# spi-interface-TFML.net
KiCad netlist of a schematic drawn in EAGLE
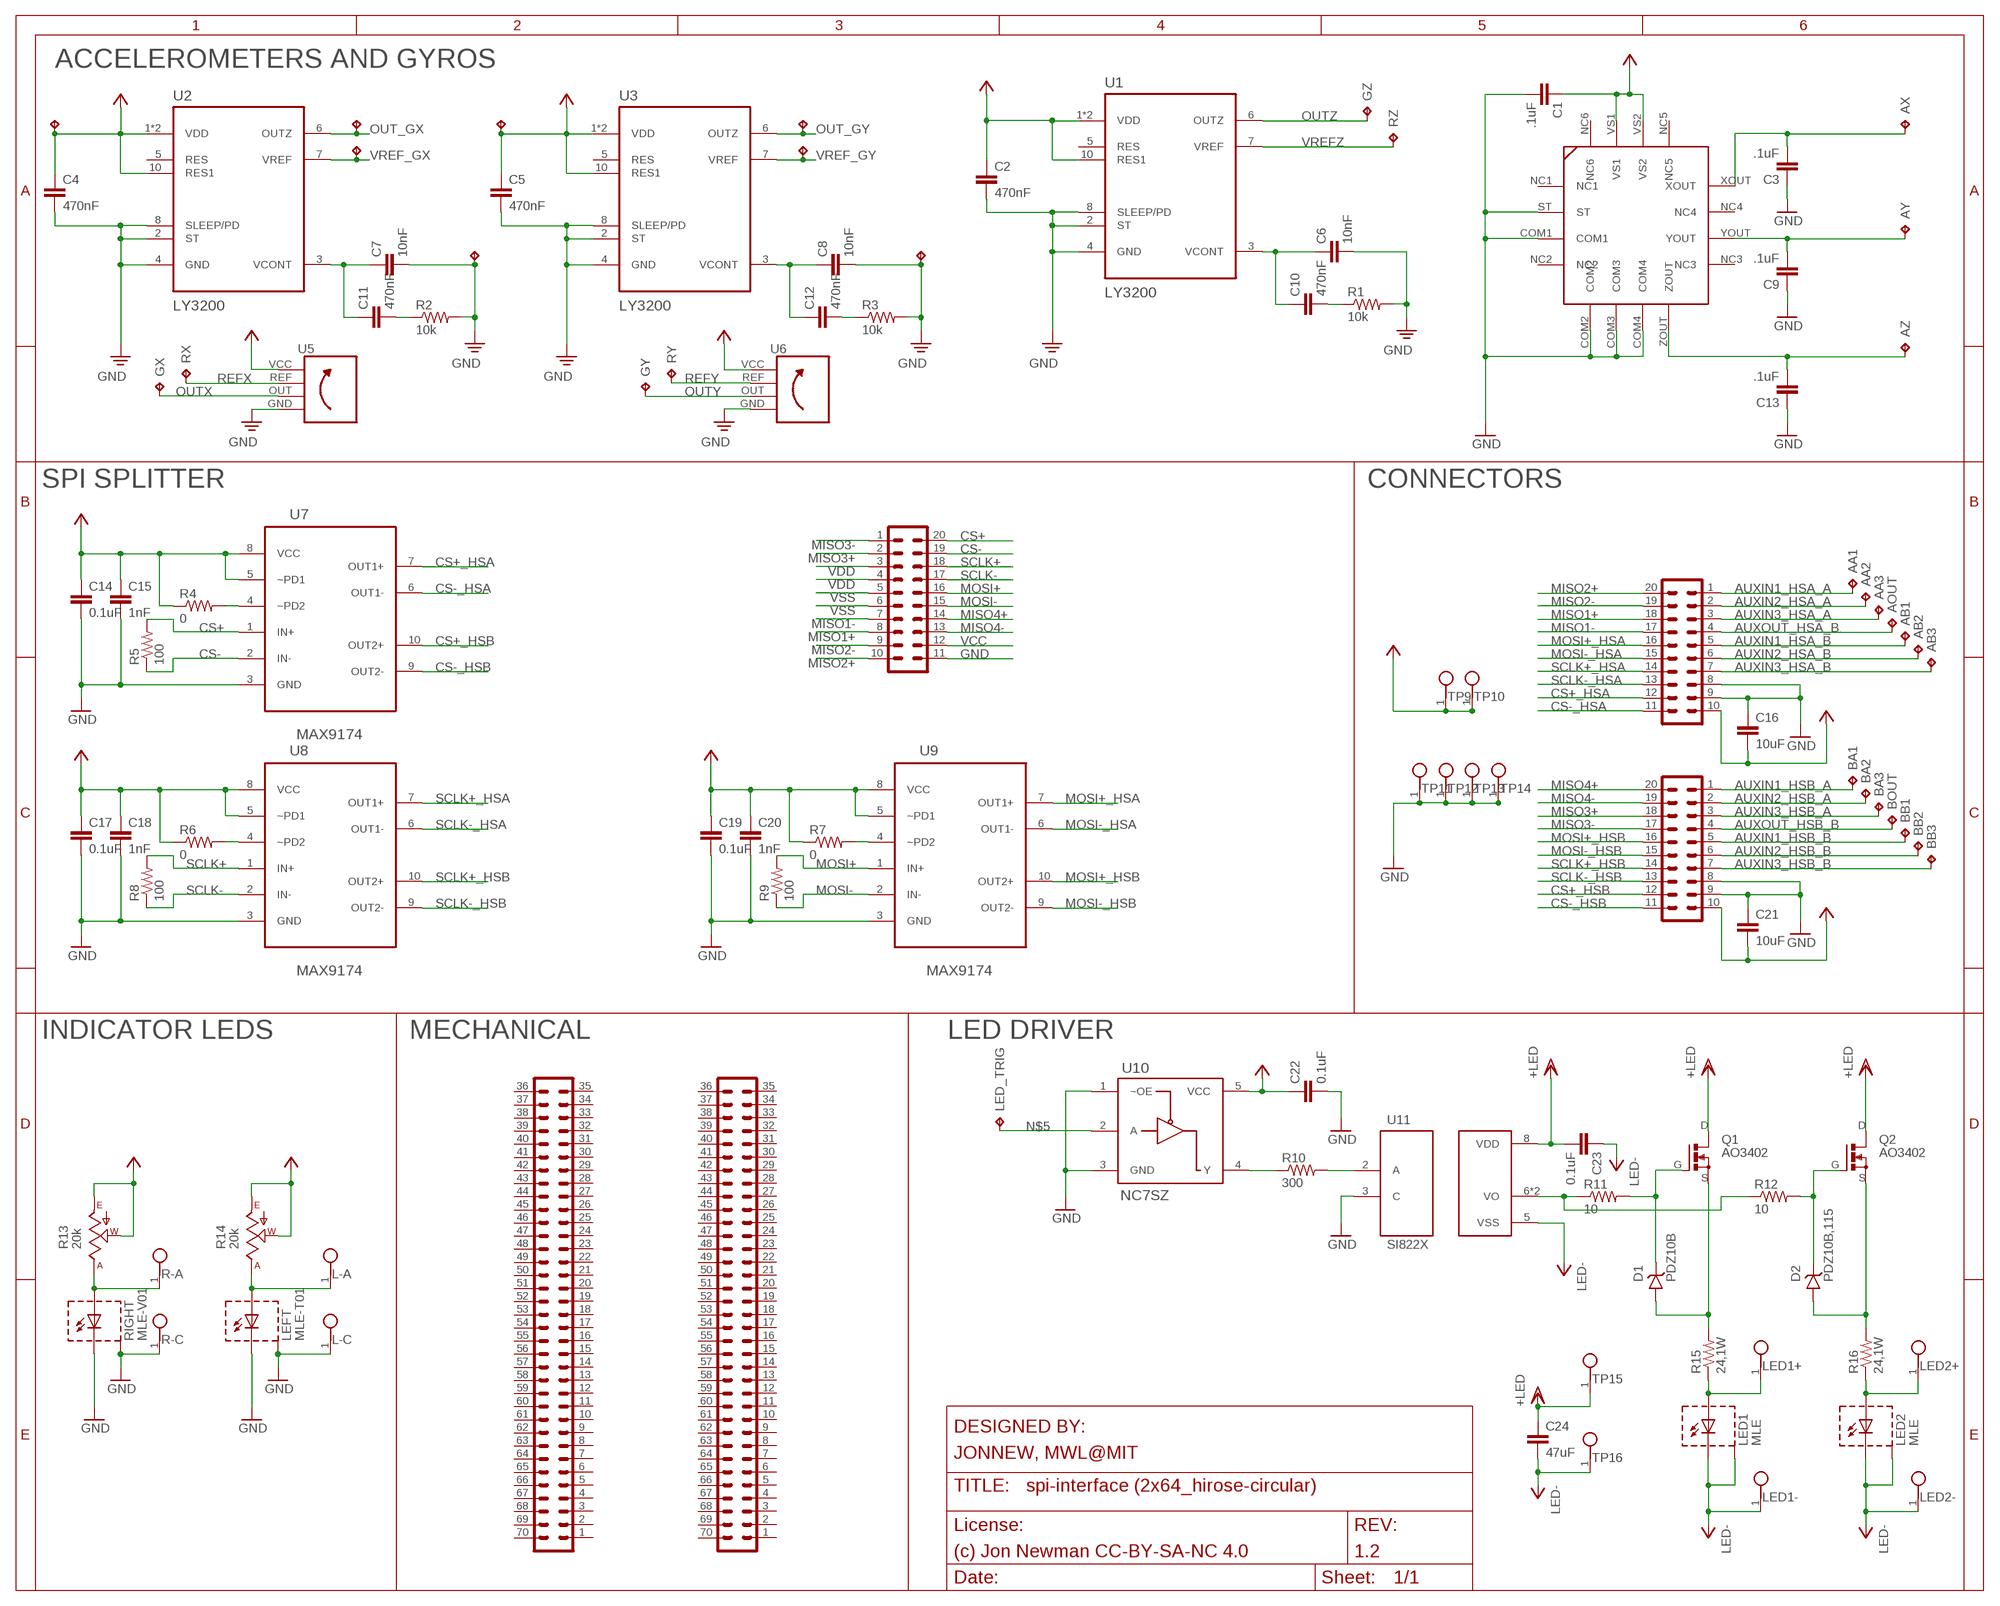
[diagram p0: schematic, sheet 1]

(export (version "E")
  (design (tool "Eeschema 10.0.6"))
  (components
    (comp (ref "AA1")
      (value "TP_0.5MM")
      (footprint "eagle-import:TESTPOINT_0.5MM")
      (libsource (lib "eagle-import") (part "TP_0.5MM"))
    )
    (comp (ref "AA2")
      (value "TP_0.5MM")
      (footprint "eagle-import:TESTPOINT_0.5MM")
      (libsource (lib "eagle-import") (part "TP_0.5MM"))
    )
    (comp (ref "AA3")
      (value "TP_0.5MM")
      (footprint "eagle-import:TESTPOINT_0.5MM")
      (libsource (lib "eagle-import") (part "TP_0.5MM"))
    )
    (comp (ref "AB1")
      (value "TP_0.5MM")
      (footprint "eagle-import:TESTPOINT_0.5MM")
      (libsource (lib "eagle-import") (part "TP_0.5MM"))
    )
    (comp (ref "AB2")
      (value "TP_0.5MM")
      (footprint "eagle-import:TESTPOINT_0.5MM")
      (libsource (lib "eagle-import") (part "TP_0.5MM"))
    )
    (comp (ref "AB3")
      (value "TP_0.5MM")
      (footprint "eagle-import:TESTPOINT_0.5MM")
      (libsource (lib "eagle-import") (part "TP_0.5MM"))
    )
    (comp (ref "AOUT")
      (value "TP_0.5MM")
      (footprint "eagle-import:TESTPOINT_0.5MM")
      (libsource (lib "eagle-import") (part "TP_0.5MM"))
    )
    (comp (ref "AX")
      (value "TP_0.5MM")
      (footprint "eagle-import:TESTPOINT_0.5MM")
      (libsource (lib "eagle-import") (part "TP_0.5MM"))
    )
    (comp (ref "AY")
      (value "TP_0.5MM")
      (footprint "eagle-import:TESTPOINT_0.5MM")
      (libsource (lib "eagle-import") (part "TP_0.5MM"))
    )
    (comp (ref "AZ")
      (value "TP_0.5MM")
      (footprint "eagle-import:TESTPOINT_0.5MM")
      (libsource (lib "eagle-import") (part "TP_0.5MM"))
    )
    (comp (ref "BA1")
      (value "TP_0.5MM")
      (footprint "eagle-import:TESTPOINT_0.5MM")
      (libsource (lib "eagle-import") (part "TP_0.5MM"))
    )
    (comp (ref "BA2")
      (value "TP_0.5MM")
      (footprint "eagle-import:TESTPOINT_0.5MM")
      (libsource (lib "eagle-import") (part "TP_0.5MM"))
    )
    (comp (ref "BA3")
      (value "TP_0.5MM")
      (footprint "eagle-import:TESTPOINT_0.5MM")
      (libsource (lib "eagle-import") (part "TP_0.5MM"))
    )
    (comp (ref "BB1")
      (value "TP_0.5MM")
      (footprint "eagle-import:TESTPOINT_0.5MM")
      (libsource (lib "eagle-import") (part "TP_0.5MM"))
    )
    (comp (ref "BB2")
      (value "TP_0.5MM")
      (footprint "eagle-import:TESTPOINT_0.5MM")
      (libsource (lib "eagle-import") (part "TP_0.5MM"))
    )
    (comp (ref "BB3")
      (value "TP_0.5MM")
      (footprint "eagle-import:TESTPOINT_0.5MM")
      (libsource (lib "eagle-import") (part "TP_0.5MM"))
    )
    (comp (ref "BOUT")
      (value "TP_0.5MM")
      (footprint "eagle-import:TESTPOINT_0.5MM")
      (libsource (lib "eagle-import") (part "TP_0.5MM"))
    )
    (comp (ref "C1")
      (value ".1uF")
      (footprint "eagle-import:0402")
      (libsource (lib "eagle-import") (part "C_0402"))
    )
    (comp (ref "C2")
      (value "470nF")
      (footprint "eagle-import:0201")
      (libsource (lib "eagle-import") (part "jonnew_C_0201"))
    )
    (comp (ref "C3")
      (value ".1uF")
      (footprint "eagle-import:0201")
      (libsource (lib "eagle-import") (part "jonnew_C_0201"))
    )
    (comp (ref "C4")
      (value "470nF")
      (footprint "eagle-import:0201")
      (libsource (lib "eagle-import") (part "jonnew_C_0201"))
    )
    (comp (ref "C5")
      (value "470nF")
      (footprint "eagle-import:0201")
      (libsource (lib "eagle-import") (part "jonnew_C_0201"))
    )
    (comp (ref "C6")
      (value "10nF")
      (footprint "eagle-import:0201")
      (libsource (lib "eagle-import") (part "jonnew_C_0201"))
    )
    (comp (ref "C7")
      (value "10nF")
      (footprint "eagle-import:0201")
      (libsource (lib "eagle-import") (part "jonnew_C_0201"))
    )
    (comp (ref "C8")
      (value "10nF")
      (footprint "eagle-import:0201")
      (libsource (lib "eagle-import") (part "jonnew_C_0201"))
    )
    (comp (ref "C9")
      (value ".1uF")
      (footprint "eagle-import:0201")
      (libsource (lib "eagle-import") (part "jonnew_C_0201"))
    )
    (comp (ref "C10")
      (value "470nF")
      (footprint "eagle-import:0201")
      (libsource (lib "eagle-import") (part "jonnew_C_0201"))
    )
    (comp (ref "C11")
      (value "470nF")
      (footprint "eagle-import:0201")
      (libsource (lib "eagle-import") (part "jonnew_C_0201"))
    )
    (comp (ref "C12")
      (value "470nF")
      (footprint "eagle-import:0201")
      (libsource (lib "eagle-import") (part "jonnew_C_0201"))
    )
    (comp (ref "C13")
      (value ".1uF")
      (footprint "eagle-import:0201")
      (libsource (lib "eagle-import") (part "jonnew_C_0201"))
    )
    (comp (ref "C14")
      (value "0.1uF")
      (footprint "eagle-import:0402")
      (libsource (lib "eagle-import") (part "jonnew_C_0402"))
    )
    (comp (ref "C15")
      (value "1nF")
      (footprint "eagle-import:0201")
      (libsource (lib "eagle-import") (part "jonnew_C_0201"))
    )
    (comp (ref "C16")
      (value "10uF")
      (footprint "eagle-import:0805")
      (fields (field (name "PARTNO") "C2012X5R1Cxxxxxxx"))
      (libsource (lib "eagle-import") (part "C_0805"))
    )
    (comp (ref "C17")
      (value "0.1uF")
      (footprint "eagle-import:0402")
      (libsource (lib "eagle-import") (part "jonnew_C_0402"))
    )
    (comp (ref "C18")
      (value "1nF")
      (footprint "eagle-import:0201")
      (libsource (lib "eagle-import") (part "jonnew_C_0201"))
    )
    (comp (ref "C19")
      (value "0.1uF")
      (footprint "eagle-import:0402")
      (libsource (lib "eagle-import") (part "jonnew_C_0402"))
    )
    (comp (ref "C20")
      (value "1nF")
      (footprint "eagle-import:0201")
      (libsource (lib "eagle-import") (part "jonnew_C_0201"))
    )
    (comp (ref "C21")
      (value "10uF")
      (footprint "eagle-import:0805")
      (fields (field (name "PARTNO") "C2012X5R1Cxxxxxxx"))
      (libsource (lib "eagle-import") (part "C_0805"))
    )
    (comp (ref "C22")
      (value "0.1uF")
      (footprint "eagle-import:0402")
      (libsource (lib "eagle-import") (part "jonnew_C_0402"))
    )
    (comp (ref "C23")
      (value "0.1uF")
      (footprint "eagle-import:0402")
      (libsource (lib "eagle-import") (part "jonnew_C_0402"))
    )
    (comp (ref "C24")
      (value "47uF")
      (footprint "eagle-import:1206")
      (libsource (lib "eagle-import") (part "jonnew_C_1206"))
    )
    (comp (ref "D1")
      (value "PDZ10B")
      (footprint "eagle-import:SOD-323")
      (libsource (lib "eagle-import") (part "Z-DIODE_SOD-323"))
    )
    (comp (ref "D2")
      (value "PDZ10B,115")
      (footprint "eagle-import:SOD-323")
      (libsource (lib "eagle-import") (part "Z-DIODE_SOD-323"))
    )
    (comp (ref "DIO_HSA")
      (value "PINHD-2X10_DF40-20REC")
      (footprint "eagle-import:DF40-20REC")
      (libsource (lib "eagle-import") (part "PINHD-2X10_DF40-20REC"))
    )
    (comp (ref "DIO_HSB")
      (value "PINHD-2X10_DF40-20REC")
      (footprint "eagle-import:DF40-20REC")
      (libsource (lib "eagle-import") (part "PINHD-2X10_DF40-20REC"))
    )
    (comp (ref "GX")
      (value "TP_0.5MM")
      (footprint "eagle-import:TESTPOINT_0.5MM")
      (libsource (lib "eagle-import") (part "TP_0.5MM"))
    )
    (comp (ref "GY")
      (value "TP_0.5MM")
      (footprint "eagle-import:TESTPOINT_0.5MM")
      (libsource (lib "eagle-import") (part "TP_0.5MM"))
    )
    (comp (ref "GZ")
      (value "TP_0.5MM")
      (footprint "eagle-import:TESTPOINT_0.5MM")
      (libsource (lib "eagle-import") (part "TP_0.5MM"))
    )
    (comp (ref "L-A")
      (value "TESTPOINT_SMALL")
      (footprint "eagle-import:TESTPOINT_SMALL")
      (libsource (lib "eagle-import") (part "TESTPOINT_SMALL"))
    )
    (comp (ref "L-C")
      (value "TESTPOINT_SMALL")
      (footprint "eagle-import:TESTPOINT_SMALL")
      (libsource (lib "eagle-import") (part "TESTPOINT_SMALL"))
    )
    (comp (ref "LED1")
      (value "MLE")
      (footprint "eagle-import:LED-MLE")
      (libsource (lib "eagle-import") (part "LED_PKG-BODY"))
    )
    (comp (ref "LED1+")
      (value "TESTPOINT_SMALL")
      (footprint "eagle-import:TESTPOINT_SMALL")
      (libsource (lib "eagle-import") (part "TESTPOINT_SMALL"))
    )
    (comp (ref "LED1-")
      (value "TESTPOINT_SMALL")
      (footprint "eagle-import:TESTPOINT_SMALL")
      (libsource (lib "eagle-import") (part "TESTPOINT_SMALL"))
    )
    (comp (ref "LED2")
      (value "MLE")
      (footprint "eagle-import:LED-MLE")
      (libsource (lib "eagle-import") (part "LED_PKG-BODY"))
    )
    (comp (ref "LED2+")
      (value "TESTPOINT_SMALL")
      (footprint "eagle-import:TESTPOINT_SMALL")
      (libsource (lib "eagle-import") (part "TESTPOINT_SMALL"))
    )
    (comp (ref "LED2-")
      (value "TESTPOINT_SMALL")
      (footprint "eagle-import:TESTPOINT_SMALL")
      (libsource (lib "eagle-import") (part "TESTPOINT_SMALL"))
    )
    (comp (ref "LED_TRIG")
      (value "TP_0.5MM")
      (footprint "eagle-import:TESTPOINT_0.5MM")
      (libsource (lib "eagle-import") (part "TP_0.5MM"))
    )
    (comp (ref "LEFT")
      (value "MLE-T01")
      (footprint "eagle-import:LED-MLE")
      (libsource (lib "eagle-import") (part "LED_PKG-BODY"))
    )
    (comp (ref "MECH_E0B")
      (value "PINHD-2X35_DF40REC")
      (footprint "eagle-import:DF40-70REC")
      (libsource (lib "eagle-import") (part "PINHD-2X35_DF40REC"))
    )
    (comp (ref "MECH_W0B")
      (value "PINHD-2X35_DF40REC")
      (footprint "eagle-import:DF40-70REC")
      (libsource (lib "eagle-import") (part "PINHD-2X35_DF40REC"))
    )
    (comp (ref "Q1")
      (value "AO3402")
      (footprint "eagle-import:SOT23-GSD")
      (libsource (lib "eagle-import") (part "N-MOSFET_SOT23-GSD"))
    )
    (comp (ref "Q2")
      (value "AO3402")
      (footprint "eagle-import:SOT23-GSD")
      (libsource (lib "eagle-import") (part "N-MOSFET_SOT23-GSD"))
    )
    (comp (ref "R-A")
      (value "TESTPOINT_SMALL")
      (footprint "eagle-import:TESTPOINT_SMALL")
      (libsource (lib "eagle-import") (part "TESTPOINT_SMALL"))
    )
    (comp (ref "R-C")
      (value "TESTPOINT_SMALL")
      (footprint "eagle-import:TESTPOINT_SMALL")
      (libsource (lib "eagle-import") (part "TESTPOINT_SMALL"))
    )
    (comp (ref "R1")
      (value "10k")
      (footprint "eagle-import:0201")
      (libsource (lib "eagle-import") (part "R_0201"))
    )
    (comp (ref "R2")
      (value "10k")
      (footprint "eagle-import:0201")
      (libsource (lib "eagle-import") (part "R_0201"))
    )
    (comp (ref "R3")
      (value "10k")
      (footprint "eagle-import:0201")
      (libsource (lib "eagle-import") (part "R_0201"))
    )
    (comp (ref "R4")
      (value "0")
      (footprint "eagle-import:0201")
      (libsource (lib "eagle-import") (part "R_0201"))
    )
    (comp (ref "R5")
      (value "100")
      (footprint "eagle-import:0201")
      (libsource (lib "eagle-import") (part "R_0201"))
    )
    (comp (ref "R6")
      (value "0")
      (footprint "eagle-import:0201")
      (libsource (lib "eagle-import") (part "R_0201"))
    )
    (comp (ref "R7")
      (value "0")
      (footprint "eagle-import:0201")
      (libsource (lib "eagle-import") (part "R_0201"))
    )
    (comp (ref "R8")
      (value "100")
      (footprint "eagle-import:0201")
      (libsource (lib "eagle-import") (part "R_0201"))
    )
    (comp (ref "R9")
      (value "100")
      (footprint "eagle-import:0201")
      (libsource (lib "eagle-import") (part "R_0201"))
    )
    (comp (ref "R10")
      (value "300")
      (footprint "eagle-import:0402")
      (libsource (lib "eagle-import") (part "R_0402"))
    )
    (comp (ref "R11")
      (value "10")
      (footprint "eagle-import:0402")
      (libsource (lib "eagle-import") (part "R_0402"))
    )
    (comp (ref "R12")
      (value "10")
      (footprint "eagle-import:0402")
      (libsource (lib "eagle-import") (part "R_0402"))
    )
    (comp (ref "R13")
      (value "20k")
      (footprint "eagle-import:SM-42_43W")
      (libsource (lib "eagle-import") (part "TRIM_US-SM-42/43W"))
    )
    (comp (ref "R14")
      (value "20k")
      (footprint "eagle-import:SM-42_43W")
      (libsource (lib "eagle-import") (part "TRIM_US-SM-42/43W"))
    )
    (comp (ref "R15")
      (value "24,1W")
      (footprint "eagle-import:0805")
      (libsource (lib "eagle-import") (part "R_0805"))
    )
    (comp (ref "R16")
      (value "24,1W")
      (footprint "eagle-import:0805")
      (libsource (lib "eagle-import") (part "R_0805"))
    )
    (comp (ref "RIGHT")
      (value "MLE-V01")
      (footprint "eagle-import:LED-MLE")
      (libsource (lib "eagle-import") (part "LED_PKG-BODY"))
    )
    (comp (ref "RX")
      (value "TP_0.5MM")
      (footprint "eagle-import:TESTPOINT_0.5MM")
      (libsource (lib "eagle-import") (part "TP_0.5MM"))
    )
    (comp (ref "RY")
      (value "TP_0.5MM")
      (footprint "eagle-import:TESTPOINT_0.5MM")
      (libsource (lib "eagle-import") (part "TP_0.5MM"))
    )
    (comp (ref "RZ")
      (value "TP_0.5MM")
      (footprint "eagle-import:TESTPOINT_0.5MM")
      (libsource (lib "eagle-import") (part "TP_0.5MM"))
    )
    (comp (ref "TETHER")
      (value "TFML-110-01-S-D-LC")
      (footprint "eagle-import:TFML-110-01-2-D-LC")
      (libsource (lib "eagle-import") (part "PINHD-2X10_TFML"))
    )
    (comp (ref "TP1")
      (value "TPTP08SQ")
      (footprint "eagle-import:TP08SQ")
      (libsource (lib "eagle-import") (part "TPTP08SQ"))
    )
    (comp (ref "TP2")
      (value "TPTP08SQ")
      (footprint "eagle-import:TP08SQ")
      (libsource (lib "eagle-import") (part "TPTP08SQ"))
    )
    (comp (ref "TP3")
      (value "TPTP08SQ")
      (footprint "eagle-import:TP08SQ")
      (libsource (lib "eagle-import") (part "TPTP08SQ"))
    )
    (comp (ref "TP4")
      (value "TPTP08SQ")
      (footprint "eagle-import:TP08SQ")
      (libsource (lib "eagle-import") (part "TPTP08SQ"))
    )
    (comp (ref "TP5")
      (value "TPTP08SQ")
      (footprint "eagle-import:TP08SQ")
      (libsource (lib "eagle-import") (part "TPTP08SQ"))
    )
    (comp (ref "TP6")
      (value "TPTP08SQ")
      (footprint "eagle-import:TP08SQ")
      (libsource (lib "eagle-import") (part "TPTP08SQ"))
    )
    (comp (ref "TP7")
      (value "TPTP08SQ")
      (footprint "eagle-import:TP08SQ")
      (libsource (lib "eagle-import") (part "TPTP08SQ"))
    )
    (comp (ref "TP8")
      (value "TPTP08SQ")
      (footprint "eagle-import:TP08SQ")
      (libsource (lib "eagle-import") (part "TPTP08SQ"))
    )
    (comp (ref "TP9")
      (value "TESTPOINT_SMALL")
      (footprint "eagle-import:TESTPOINT_SMALL")
      (libsource (lib "eagle-import") (part "TESTPOINT_SMALL"))
    )
    (comp (ref "TP10")
      (value "TESTPOINT_SMALL")
      (footprint "eagle-import:TESTPOINT_SMALL")
      (libsource (lib "eagle-import") (part "TESTPOINT_SMALL"))
    )
    (comp (ref "TP11")
      (value "TESTPOINT_SMALL")
      (footprint "eagle-import:TESTPOINT_SMALL")
      (libsource (lib "eagle-import") (part "TESTPOINT_SMALL"))
    )
    (comp (ref "TP12")
      (value "TESTPOINT_SMALL")
      (footprint "eagle-import:TESTPOINT_SMALL")
      (libsource (lib "eagle-import") (part "TESTPOINT_SMALL"))
    )
    (comp (ref "TP13")
      (value "TESTPOINT_SMALL")
      (footprint "eagle-import:TESTPOINT_SMALL")
      (libsource (lib "eagle-import") (part "TESTPOINT_SMALL"))
    )
    (comp (ref "TP14")
      (value "TESTPOINT_SMALL")
      (footprint "eagle-import:TESTPOINT_SMALL")
      (libsource (lib "eagle-import") (part "TESTPOINT_SMALL"))
    )
    (comp (ref "TP15")
      (value "TESTPOINT_SMALL")
      (footprint "eagle-import:TESTPOINT_SMALL")
      (libsource (lib "eagle-import") (part "TESTPOINT_SMALL"))
    )
    (comp (ref "TP16")
      (value "TESTPOINT_SMALL")
      (footprint "eagle-import:TESTPOINT_SMALL")
      (libsource (lib "eagle-import") (part "TESTPOINT_SMALL"))
    )
    (comp (ref "U1")
      (value "LY3200")
      (footprint "eagle-import:LGA-10-COMPACT")
      (libsource (lib "eagle-import") (part "LY3200ALH_LGA-10-COMPACT"))
    )
    (comp (ref "U2")
      (value "LY3200")
      (footprint "eagle-import:LGA-10-COMPACT")
      (libsource (lib "eagle-import") (part "LY3200ALH_LGA-10-COMPACT"))
    )
    (comp (ref "U3")
      (value "LY3200")
      (footprint "eagle-import:LGA-10-COMPACT")
      (libsource (lib "eagle-import") (part "LY3200ALH_LGA-10-COMPACT"))
    )
    (comp (ref "U4")
      (value "ADXL335")
      (footprint "eagle-import:ADXL335")
      (libsource (lib "eagle-import") (part "ADXL335"))
    )
    (comp (ref "U5")
      (value "LY3200-VERT-MODULE")
      (footprint "eagle-import:LY3200-VERT-MODULE")
      (libsource (lib "eagle-import") (part "LY3200-VERT-MODULE"))
    )
    (comp (ref "U6")
      (value "LY3200-VERT-MODULE")
      (footprint "eagle-import:LY3200-VERT-MODULE")
      (libsource (lib "eagle-import") (part "LY3200-VERT-MODULE"))
    )
    (comp (ref "U7")
      (value "MAX9174")
      (footprint "eagle-import:10-UMAX")
      (libsource (lib "eagle-import") (part "MAX9174_UMAX"))
    )
    (comp (ref "U8")
      (value "MAX9174")
      (footprint "eagle-import:10-UMAX")
      (libsource (lib "eagle-import") (part "MAX9174_UMAX"))
    )
    (comp (ref "U9")
      (value "MAX9174")
      (footprint "eagle-import:10-UMAX")
      (libsource (lib "eagle-import") (part "MAX9174_UMAX"))
    )
    (comp (ref "U10")
      (value "NC7SZ")
      (footprint "eagle-import:SOT-23-5")
      (libsource (lib "eagle-import") (part "NC7SZ125"))
    )
    (comp (ref "U11")
      (value "SI822X")
      (footprint "eagle-import:SOIC127P500X400-8N")
      (libsource (lib "eagle-import") (part "SI822X"))
    )
  )
  (nets
    (net (code "1") (name "+LED") (class "Default")
      (node (ref "C23") (pin "2") (pinfunction "2_2") (pintype "passive"))
      (node (ref "C24") (pin "1") (pinfunction "1_1") (pintype "passive"))
      (node (ref "Q1") (pin "D") (pinfunction "D_D") (pintype "bidirectional"))
      (node (ref "Q2") (pin "D") (pinfunction "D_D") (pintype "bidirectional"))
      (node (ref "TETHER") (pin "3") (pinfunction "3_3") (pintype "bidirectional"))
      (node (ref "TETHER") (pin "4") (pinfunction "4_4") (pintype "bidirectional"))
      (node (ref "TP15") (pin "1") (pinfunction "1_1") (pintype "passive"))
      (node (ref "U11") (pin "8") (pinfunction "VDD_8") (pintype "power_in"))
    )
    (net (code "2") (name "/AUXIN1_HSA_A") (class "Default")
      (node (ref "AA1") (pin "1") (pinfunction "TP_1") (pintype "input"))
      (node (ref "DIO_HSA") (pin "1") (pinfunction "1_1") (pintype "bidirectional"))
    )
    (net (code "3") (name "/AUXIN1_HSA_B") (class "Default")
      (node (ref "AB1") (pin "1") (pinfunction "TP_1") (pintype "input"))
      (node (ref "DIO_HSA") (pin "5") (pinfunction "5_5") (pintype "bidirectional"))
    )
    (net (code "4") (name "/AUXIN1_HSB_A") (class "Default")
      (node (ref "BA1") (pin "1") (pinfunction "TP_1") (pintype "input"))
      (node (ref "DIO_HSB") (pin "1") (pinfunction "1_1") (pintype "bidirectional"))
    )
    (net (code "5") (name "/AUXIN1_HSB_B") (class "Default")
      (node (ref "BB1") (pin "1") (pinfunction "TP_1") (pintype "input"))
      (node (ref "DIO_HSB") (pin "5") (pinfunction "5_5") (pintype "bidirectional"))
    )
    (net (code "6") (name "/AUXIN2_HSA_A") (class "Default")
      (node (ref "AA2") (pin "1") (pinfunction "TP_1") (pintype "input"))
      (node (ref "DIO_HSA") (pin "2") (pinfunction "2_2") (pintype "bidirectional"))
    )
    (net (code "7") (name "/AUXIN2_HSA_B") (class "Default")
      (node (ref "AB2") (pin "1") (pinfunction "TP_1") (pintype "input"))
      (node (ref "DIO_HSA") (pin "6") (pinfunction "6_6") (pintype "bidirectional"))
    )
    (net (code "8") (name "/AUXIN2_HSB_A") (class "Default")
      (node (ref "BA2") (pin "1") (pinfunction "TP_1") (pintype "input"))
      (node (ref "DIO_HSB") (pin "2") (pinfunction "2_2") (pintype "bidirectional"))
    )
    (net (code "9") (name "/AUXIN2_HSB_B") (class "Default")
      (node (ref "BB2") (pin "1") (pinfunction "TP_1") (pintype "input"))
      (node (ref "DIO_HSB") (pin "6") (pinfunction "6_6") (pintype "bidirectional"))
    )
    (net (code "10") (name "/AUXIN3_HSA_A") (class "Default")
      (node (ref "AA3") (pin "1") (pinfunction "TP_1") (pintype "input"))
      (node (ref "DIO_HSA") (pin "3") (pinfunction "3_3") (pintype "bidirectional"))
    )
    (net (code "11") (name "/AUXIN3_HSA_B") (class "Default")
      (node (ref "AB3") (pin "1") (pinfunction "TP_1") (pintype "input"))
      (node (ref "DIO_HSA") (pin "7") (pinfunction "7_7") (pintype "bidirectional"))
    )
    (net (code "12") (name "/AUXIN3_HSB_A") (class "Default")
      (node (ref "BA3") (pin "1") (pinfunction "TP_1") (pintype "input"))
      (node (ref "DIO_HSB") (pin "3") (pinfunction "3_3") (pintype "bidirectional"))
    )
    (net (code "13") (name "/AUXIN3_HSB_B") (class "Default")
      (node (ref "BB3") (pin "1") (pinfunction "TP_1") (pintype "input"))
      (node (ref "DIO_HSB") (pin "7") (pinfunction "7_7") (pintype "bidirectional"))
    )
    (net (code "14") (name "/AUXOUT_HSA_B") (class "Default")
      (node (ref "AOUT") (pin "1") (pinfunction "TP_1") (pintype "input"))
      (node (ref "DIO_HSA") (pin "4") (pinfunction "4_4") (pintype "bidirectional"))
    )
    (net (code "15") (name "/AUXOUT_HSB_B") (class "Default")
      (node (ref "BOUT") (pin "1") (pinfunction "TP_1") (pintype "input"))
      (node (ref "DIO_HSB") (pin "4") (pinfunction "4_4") (pintype "bidirectional"))
    )
    (net (code "16") (name "/CS+") (class "Default")
      (node (ref "R5") (pin "2") (pinfunction "2_2") (pintype "passive"))
      (node (ref "TETHER") (pin "20") (pinfunction "20_20") (pintype "bidirectional"))
      (node (ref "U7") (pin "1") (pinfunction "IN+_1") (pintype "input"))
    )
    (net (code "17") (name "/CS+_HSA") (class "Default")
      (node (ref "DIO_HSA") (pin "12") (pinfunction "12_12") (pintype "bidirectional"))
      (node (ref "U7") (pin "7") (pinfunction "OUT1+_7") (pintype "output"))
    )
    (net (code "18") (name "/CS+_HSB") (class "Default")
      (node (ref "DIO_HSB") (pin "12") (pinfunction "12_12") (pintype "bidirectional"))
      (node (ref "U7") (pin "10") (pinfunction "OUT2+_10") (pintype "output"))
    )
    (net (code "19") (name "/CS-") (class "Default")
      (node (ref "R5") (pin "1") (pinfunction "1_1") (pintype "passive"))
      (node (ref "TETHER") (pin "19") (pinfunction "19_19") (pintype "bidirectional"))
      (node (ref "U7") (pin "2") (pinfunction "IN-_2") (pintype "input"))
    )
    (net (code "20") (name "/CS-_HSA") (class "Default")
      (node (ref "DIO_HSA") (pin "11") (pinfunction "11_11") (pintype "bidirectional"))
      (node (ref "U7") (pin "6") (pinfunction "OUT1-_6") (pintype "output"))
    )
    (net (code "21") (name "/CS-_HSB") (class "Default")
      (node (ref "DIO_HSB") (pin "11") (pinfunction "11_11") (pintype "bidirectional"))
      (node (ref "U7") (pin "9") (pinfunction "OUT2-_9") (pintype "output"))
    )
    (net (code "22") (name "/MISO1+") (class "Default")
      (node (ref "DIO_HSA") (pin "18") (pinfunction "18_18") (pintype "bidirectional"))
      (node (ref "TETHER") (pin "8") (pinfunction "8_8") (pintype "bidirectional"))
    )
    (net (code "23") (name "/MISO1-") (class "Default")
      (node (ref "DIO_HSA") (pin "17") (pinfunction "17_17") (pintype "bidirectional"))
      (node (ref "TETHER") (pin "7") (pinfunction "7_7") (pintype "bidirectional"))
    )
    (net (code "24") (name "/MISO2+") (class "Default")
      (node (ref "DIO_HSA") (pin "20") (pinfunction "20_20") (pintype "bidirectional"))
      (node (ref "TETHER") (pin "10") (pinfunction "10_10") (pintype "bidirectional"))
    )
    (net (code "25") (name "/MISO2-") (class "Default")
      (node (ref "DIO_HSA") (pin "19") (pinfunction "19_19") (pintype "bidirectional"))
      (node (ref "TETHER") (pin "9") (pinfunction "9_9") (pintype "bidirectional"))
    )
    (net (code "26") (name "/MISO3+") (class "Default")
      (node (ref "DIO_HSB") (pin "18") (pinfunction "18_18") (pintype "bidirectional"))
      (node (ref "TETHER") (pin "2") (pinfunction "2_2") (pintype "bidirectional"))
    )
    (net (code "27") (name "/MISO3-") (class "Default")
      (node (ref "DIO_HSB") (pin "17") (pinfunction "17_17") (pintype "bidirectional"))
      (node (ref "TETHER") (pin "1") (pinfunction "1_1") (pintype "bidirectional"))
    )
    (net (code "28") (name "/MISO4+") (class "Default")
      (node (ref "DIO_HSB") (pin "20") (pinfunction "20_20") (pintype "bidirectional"))
      (node (ref "TETHER") (pin "14") (pinfunction "14_14") (pintype "bidirectional"))
    )
    (net (code "29") (name "/MISO4-") (class "Default")
      (node (ref "DIO_HSB") (pin "19") (pinfunction "19_19") (pintype "bidirectional"))
      (node (ref "TETHER") (pin "13") (pinfunction "13_13") (pintype "bidirectional"))
    )
    (net (code "30") (name "/MOSI+") (class "Default")
      (node (ref "R9") (pin "2") (pinfunction "2_2") (pintype "passive"))
      (node (ref "TETHER") (pin "16") (pinfunction "16_16") (pintype "bidirectional"))
      (node (ref "U9") (pin "1") (pinfunction "IN+_1") (pintype "input"))
    )
    (net (code "31") (name "/MOSI+_HSA") (class "Default")
      (node (ref "DIO_HSA") (pin "16") (pinfunction "16_16") (pintype "bidirectional"))
      (node (ref "U9") (pin "7") (pinfunction "OUT1+_7") (pintype "output"))
    )
    (net (code "32") (name "/MOSI+_HSB") (class "Default")
      (node (ref "DIO_HSB") (pin "16") (pinfunction "16_16") (pintype "bidirectional"))
      (node (ref "U9") (pin "10") (pinfunction "OUT2+_10") (pintype "output"))
    )
    (net (code "33") (name "/MOSI-") (class "Default")
      (node (ref "R9") (pin "1") (pinfunction "1_1") (pintype "passive"))
      (node (ref "TETHER") (pin "15") (pinfunction "15_15") (pintype "bidirectional"))
      (node (ref "U9") (pin "2") (pinfunction "IN-_2") (pintype "input"))
    )
    (net (code "34") (name "/MOSI-_HSA") (class "Default")
      (node (ref "DIO_HSA") (pin "15") (pinfunction "15_15") (pintype "bidirectional"))
      (node (ref "U9") (pin "6") (pinfunction "OUT1-_6") (pintype "output"))
    )
    (net (code "35") (name "/MOSI-_HSB") (class "Default")
      (node (ref "DIO_HSB") (pin "15") (pinfunction "15_15") (pintype "bidirectional"))
      (node (ref "U9") (pin "9") (pinfunction "OUT2-_9") (pintype "output"))
    )
    (net (code "36") (name "/N$5") (class "Default")
      (node (ref "LED_TRIG") (pin "1") (pinfunction "TP_1") (pintype "input"))
      (node (ref "U10") (pin "2") (pinfunction "A_2") (pintype "input"))
    )
    (net (code "37") (name "/OUTX") (class "Default")
      (node (ref "GX") (pin "1") (pinfunction "TP_1") (pintype "input"))
      (node (ref "U5") (pin "OUT") (pinfunction "OUT_OUT") (pintype "output"))
    )
    (net (code "38") (name "/OUTY") (class "Default")
      (node (ref "GY") (pin "1") (pinfunction "TP_1") (pintype "input"))
      (node (ref "U6") (pin "OUT") (pinfunction "OUT_OUT") (pintype "output"))
    )
    (net (code "39") (name "/OUTZ") (class "Default")
      (node (ref "GZ") (pin "1") (pinfunction "TP_1") (pintype "input"))
      (node (ref "U1") (pin "6") (pinfunction "OUTZ_6") (pintype "output"))
    )
    (net (code "40") (name "/OUT_GX") (class "Default")
      (node (ref "TP2") (pin "TP") (pinfunction "TP_TP") (pintype "input"))
      (node (ref "U2") (pin "6") (pinfunction "OUTZ_6") (pintype "output"))
    )
    (net (code "41") (name "/OUT_GY") (class "Default")
      (node (ref "TP4") (pin "TP") (pinfunction "TP_TP") (pintype "input"))
      (node (ref "U3") (pin "6") (pinfunction "OUTZ_6") (pintype "output"))
    )
    (net (code "42") (name "/REFX") (class "Default")
      (node (ref "RX") (pin "1") (pinfunction "TP_1") (pintype "input"))
      (node (ref "U5") (pin "REF") (pinfunction "REF_REF") (pintype "output"))
    )
    (net (code "43") (name "/REFY") (class "Default")
      (node (ref "RY") (pin "1") (pinfunction "TP_1") (pintype "input"))
      (node (ref "U6") (pin "REF") (pinfunction "REF_REF") (pintype "output"))
    )
    (net (code "44") (name "/SCLK+") (class "Default")
      (node (ref "R8") (pin "2") (pinfunction "2_2") (pintype "passive"))
      (node (ref "TETHER") (pin "18") (pinfunction "18_18") (pintype "bidirectional"))
      (node (ref "U8") (pin "1") (pinfunction "IN+_1") (pintype "input"))
    )
    (net (code "45") (name "/SCLK+_HSA") (class "Default")
      (node (ref "DIO_HSA") (pin "14") (pinfunction "14_14") (pintype "bidirectional"))
      (node (ref "U8") (pin "7") (pinfunction "OUT1+_7") (pintype "output"))
    )
    (net (code "46") (name "/SCLK+_HSB") (class "Default")
      (node (ref "DIO_HSB") (pin "14") (pinfunction "14_14") (pintype "bidirectional"))
      (node (ref "U8") (pin "10") (pinfunction "OUT2+_10") (pintype "output"))
    )
    (net (code "47") (name "/SCLK-") (class "Default")
      (node (ref "R8") (pin "1") (pinfunction "1_1") (pintype "passive"))
      (node (ref "TETHER") (pin "17") (pinfunction "17_17") (pintype "bidirectional"))
      (node (ref "U8") (pin "2") (pinfunction "IN-_2") (pintype "input"))
    )
    (net (code "48") (name "/SCLK-_HSA") (class "Default")
      (node (ref "DIO_HSA") (pin "13") (pinfunction "13_13") (pintype "bidirectional"))
      (node (ref "U8") (pin "6") (pinfunction "OUT1-_6") (pintype "output"))
    )
    (net (code "49") (name "/SCLK-_HSB") (class "Default")
      (node (ref "DIO_HSB") (pin "13") (pinfunction "13_13") (pintype "bidirectional"))
      (node (ref "U8") (pin "9") (pinfunction "OUT2-_9") (pintype "output"))
    )
    (net (code "50") (name "/VREFZ") (class "Default")
      (node (ref "RZ") (pin "1") (pinfunction "TP_1") (pintype "input"))
      (node (ref "U1") (pin "7") (pinfunction "VREF_7") (pintype "output"))
    )
    (net (code "51") (name "/VREF_GX") (class "Default")
      (node (ref "TP5") (pin "TP") (pinfunction "TP_TP") (pintype "input"))
      (node (ref "U2") (pin "7") (pinfunction "VREF_7") (pintype "output"))
    )
    (net (code "52") (name "/VREF_GY") (class "Default")
      (node (ref "TP6") (pin "TP") (pinfunction "TP_TP") (pintype "input"))
      (node (ref "U3") (pin "7") (pinfunction "VREF_7") (pintype "output"))
    )
    (net (code "53") (name "GND") (class "Default")
      (node (ref "C1") (pin "2") (pinfunction "2_2") (pintype "passive"))
      (node (ref "C13") (pin "1") (pinfunction "1_1") (pintype "passive"))
      (node (ref "C14") (pin "2") (pinfunction "2_2") (pintype "passive"))
      (node (ref "C15") (pin "2") (pinfunction "2_2") (pintype "passive"))
      (node (ref "C16") (pin "1") (pinfunction "1_1") (pintype "passive"))
      (node (ref "C17") (pin "2") (pinfunction "2_2") (pintype "passive"))
      (node (ref "C18") (pin "2") (pinfunction "2_2") (pintype "passive"))
      (node (ref "C19") (pin "2") (pinfunction "2_2") (pintype "passive"))
      (node (ref "C2") (pin "2") (pinfunction "2_2") (pintype "passive"))
      (node (ref "C20") (pin "2") (pinfunction "2_2") (pintype "passive"))
      (node (ref "C21") (pin "1") (pinfunction "1_1") (pintype "passive"))
      (node (ref "C22") (pin "2") (pinfunction "2_2") (pintype "passive"))
      (node (ref "C3") (pin "1") (pinfunction "1_1") (pintype "passive"))
      (node (ref "C4") (pin "2") (pinfunction "2_2") (pintype "passive"))
      (node (ref "C5") (pin "2") (pinfunction "2_2") (pintype "passive"))
      (node (ref "C6") (pin "2") (pinfunction "2_2") (pintype "passive"))
      (node (ref "C7") (pin "2") (pinfunction "2_2") (pintype "passive"))
      (node (ref "C8") (pin "2") (pinfunction "2_2") (pintype "passive"))
      (node (ref "C9") (pin "1") (pinfunction "1_1") (pintype "passive"))
      (node (ref "DIO_HSA") (pin "8") (pinfunction "8_8") (pintype "bidirectional"))
      (node (ref "DIO_HSA") (pin "9") (pinfunction "9_9") (pintype "bidirectional"))
      (node (ref "DIO_HSB") (pin "8") (pinfunction "8_8") (pintype "bidirectional"))
      (node (ref "DIO_HSB") (pin "9") (pinfunction "9_9") (pintype "bidirectional"))
      (node (ref "L-C") (pin "1") (pinfunction "1_1") (pintype "passive"))
      (node (ref "LEFT") (pin "C1") (pinfunction "C_C1") (pintype "passive"))
      (node (ref "LEFT") (pin "C2") (pinfunction "C_C2") (pintype "passive"))
      (node (ref "LEFT") (pin "HS") (pinfunction "BODY_HS") (pintype "passive"))
      (node (ref "R-C") (pin "1") (pinfunction "1_1") (pintype "passive"))
      (node (ref "R1") (pin "2") (pinfunction "2_2") (pintype "passive"))
      (node (ref "R2") (pin "2") (pinfunction "2_2") (pintype "passive"))
      (node (ref "R3") (pin "2") (pinfunction "2_2") (pintype "passive"))
      (node (ref "RIGHT") (pin "C1") (pinfunction "C_C1") (pintype "passive"))
      (node (ref "RIGHT") (pin "C2") (pinfunction "C_C2") (pintype "passive"))
      (node (ref "RIGHT") (pin "HS") (pinfunction "BODY_HS") (pintype "passive"))
      (node (ref "TETHER") (pin "11") (pinfunction "11_11") (pintype "bidirectional"))
      (node (ref "TP11") (pin "1") (pinfunction "1_1") (pintype "passive"))
      (node (ref "TP12") (pin "1") (pinfunction "1_1") (pintype "passive"))
      (node (ref "TP13") (pin "1") (pinfunction "1_1") (pintype "passive"))
      (node (ref "TP14") (pin "1") (pinfunction "1_1") (pintype "passive"))
      (node (ref "TP7") (pin "TP") (pinfunction "TP_TP") (pintype "input"))
      (node (ref "TP8") (pin "TP") (pinfunction "TP_TP") (pintype "input"))
      (node (ref "U1") (pin "2") (pinfunction "ST_2") (pintype "bidirectional"))
      (node (ref "U1") (pin "4") (pinfunction "GND_4") (pintype "power_in"))
      (node (ref "U1") (pin "8") (pinfunction "SLEEP/PD_8") (pintype "bidirectional"))
      (node (ref "U10") (pin "1") (pinfunction "~{OE}_1") (pintype "input"))
      (node (ref "U10") (pin "3") (pinfunction "GND_3") (pintype "power_in"))
      (node (ref "U11") (pin "3") (pinfunction "C_3") (pintype "bidirectional"))
      (node (ref "U2") (pin "2") (pinfunction "ST_2") (pintype "bidirectional"))
      (node (ref "U2") (pin "4") (pinfunction "GND_4") (pintype "power_in"))
      (node (ref "U2") (pin "8") (pinfunction "SLEEP/PD_8") (pintype "bidirectional"))
      (node (ref "U3") (pin "2") (pinfunction "ST_2") (pintype "bidirectional"))
      (node (ref "U3") (pin "4") (pinfunction "GND_4") (pintype "power_in"))
      (node (ref "U3") (pin "8") (pinfunction "SLEEP/PD_8") (pintype "bidirectional"))
      (node (ref "U4") (pin "COM1") (pinfunction "COM1_COM1") (pintype "bidirectional"))
      (node (ref "U4") (pin "COM2") (pinfunction "COM2_COM2") (pintype "bidirectional"))
      (node (ref "U4") (pin "COM3") (pinfunction "COM3_COM3") (pintype "bidirectional"))
      (node (ref "U4") (pin "COM4") (pinfunction "COM4_COM4") (pintype "bidirectional"))
      (node (ref "U4") (pin "ST") (pinfunction "ST_ST") (pintype "bidirectional"))
      (node (ref "U5") (pin "GND") (pinfunction "GND_GND") (pintype "power_in"))
      (node (ref "U6") (pin "GND") (pinfunction "GND_GND") (pintype "power_in"))
      (node (ref "U7") (pin "3") (pinfunction "GND_3") (pintype "power_in"))
      (node (ref "U8") (pin "3") (pinfunction "GND_3") (pintype "power_in"))
      (node (ref "U9") (pin "3") (pinfunction "GND_3") (pintype "power_in"))
    )
    (net (code "54") (name "LED-") (class "Default")
      (node (ref "C23") (pin "1") (pinfunction "1_1") (pintype "passive"))
      (node (ref "C24") (pin "2") (pinfunction "2_2") (pintype "passive"))
      (node (ref "LED1") (pin "C1") (pinfunction "C_C1") (pintype "passive"))
      (node (ref "LED1") (pin "C2") (pinfunction "C_C2") (pintype "passive"))
      (node (ref "LED1") (pin "HS") (pinfunction "BODY_HS") (pintype "passive"))
      (node (ref "LED1-") (pin "1") (pinfunction "1_1") (pintype "passive"))
      (node (ref "LED2") (pin "C1") (pinfunction "C_C1") (pintype "passive"))
      (node (ref "LED2") (pin "C2") (pinfunction "C_C2") (pintype "passive"))
      (node (ref "LED2") (pin "HS") (pinfunction "BODY_HS") (pintype "passive"))
      (node (ref "LED2-") (pin "1") (pinfunction "1_1") (pintype "passive"))
      (node (ref "TETHER") (pin "5") (pinfunction "5_5") (pintype "bidirectional"))
      (node (ref "TETHER") (pin "6") (pinfunction "6_6") (pintype "bidirectional"))
      (node (ref "TP16") (pin "1") (pinfunction "1_1") (pintype "passive"))
      (node (ref "U11") (pin "5") (pinfunction "VSS_5") (pintype "power_in"))
    )
    (net (code "55") (name "Net-(AX-TP)") (class "Default")
      (node (ref "AX") (pin "1") (pinfunction "TP_1") (pintype "input"))
      (node (ref "C3") (pin "2") (pinfunction "2_2") (pintype "passive"))
      (node (ref "U4") (pin "XOUT") (pinfunction "XOUT_XOUT") (pintype "bidirectional"))
    )
    (net (code "56") (name "Net-(AY-TP)") (class "Default")
      (node (ref "AY") (pin "1") (pinfunction "TP_1") (pintype "input"))
      (node (ref "C9") (pin "2") (pinfunction "2_2") (pintype "passive"))
      (node (ref "U4") (pin "YOUT") (pinfunction "YOUT_YOUT") (pintype "bidirectional"))
    )
    (net (code "57") (name "Net-(AZ-TP)") (class "Default")
      (node (ref "AZ") (pin "1") (pinfunction "TP_1") (pintype "input"))
      (node (ref "C13") (pin "2") (pinfunction "2_2") (pintype "passive"))
      (node (ref "U4") (pin "ZOUT") (pinfunction "ZOUT_ZOUT") (pintype "bidirectional"))
    )
    (net (code "58") (name "Net-(C10-Pad2)") (class "Default")
      (node (ref "C10") (pin "2") (pinfunction "2_2") (pintype "passive"))
      (node (ref "R1") (pin "1") (pinfunction "1_1") (pintype "passive"))
    )
    (net (code "59") (name "Net-(C11-Pad2)") (class "Default")
      (node (ref "C11") (pin "2") (pinfunction "2_2") (pintype "passive"))
      (node (ref "R2") (pin "1") (pinfunction "1_1") (pintype "passive"))
    )
    (net (code "60") (name "Net-(C12-Pad2)") (class "Default")
      (node (ref "C12") (pin "2") (pinfunction "2_2") (pintype "passive"))
      (node (ref "R3") (pin "1") (pinfunction "1_1") (pintype "passive"))
    )
    (net (code "61") (name "Net-(D1-PadA)") (class "Default")
      (node (ref "D1") (pin "A") (pinfunction "A_A") (pintype "passive"))
      (node (ref "Q1") (pin "S") (pinfunction "S_S") (pintype "bidirectional"))
      (node (ref "R15") (pin "2") (pinfunction "2_2") (pintype "passive"))
    )
    (net (code "62") (name "Net-(D1-PadC)") (class "Default")
      (node (ref "D1") (pin "C") (pinfunction "C_C") (pintype "passive"))
      (node (ref "Q1") (pin "G") (pinfunction "G_G") (pintype "bidirectional"))
      (node (ref "R11") (pin "2") (pinfunction "2_2") (pintype "passive"))
    )
    (net (code "63") (name "Net-(D2-PadA)") (class "Default")
      (node (ref "D2") (pin "A") (pinfunction "A_A") (pintype "passive"))
      (node (ref "Q2") (pin "S") (pinfunction "S_S") (pintype "bidirectional"))
      (node (ref "R16") (pin "2") (pinfunction "2_2") (pintype "passive"))
    )
    (net (code "64") (name "Net-(D2-PadC)") (class "Default")
      (node (ref "D2") (pin "C") (pinfunction "C_C") (pintype "passive"))
      (node (ref "Q2") (pin "G") (pinfunction "G_G") (pintype "bidirectional"))
      (node (ref "R12") (pin "2") (pinfunction "2_2") (pintype "passive"))
    )
    (net (code "65") (name "Net-(LED1+-Pad1)") (class "Default")
      (node (ref "LED1") (pin "A1") (pinfunction "A_A1") (pintype "passive"))
      (node (ref "LED1") (pin "A2") (pinfunction "A_A2") (pintype "passive"))
      (node (ref "LED1+") (pin "1") (pinfunction "1_1") (pintype "passive"))
      (node (ref "R15") (pin "1") (pinfunction "1_1") (pintype "passive"))
    )
    (net (code "66") (name "Net-(LED2+-Pad1)") (class "Default")
      (node (ref "LED2") (pin "A1") (pinfunction "A_A1") (pintype "passive"))
      (node (ref "LED2") (pin "A2") (pinfunction "A_A2") (pintype "passive"))
      (node (ref "LED2+") (pin "1") (pinfunction "1_1") (pintype "passive"))
      (node (ref "R16") (pin "1") (pinfunction "1_1") (pintype "passive"))
    )
    (net (code "67") (name "Net-(R11-Pad1)") (class "Default")
      (node (ref "R11") (pin "1") (pinfunction "1_1") (pintype "passive"))
      (node (ref "R12") (pin "1") (pinfunction "1_1") (pintype "passive"))
      (node (ref "U11") (pin "6") (pinfunction "VO_6") (pintype "bidirectional"))
      (node (ref "U11") (pin "7") (pinfunction "VO_7") (pintype "bidirectional"))
    )
    (net (code "68") (name "Net-(R13-A)") (class "Default")
      (node (ref "R-A") (pin "1") (pinfunction "1_1") (pintype "passive"))
      (node (ref "R13") (pin "1") (pinfunction "A_1") (pintype "passive"))
      (node (ref "RIGHT") (pin "A1") (pinfunction "A_A1") (pintype "passive"))
      (node (ref "RIGHT") (pin "A2") (pinfunction "A_A2") (pintype "passive"))
    )
    (net (code "69") (name "Net-(R14-A)") (class "Default")
      (node (ref "L-A") (pin "1") (pinfunction "1_1") (pintype "passive"))
      (node (ref "LEFT") (pin "A1") (pinfunction "A_A1") (pintype "passive"))
      (node (ref "LEFT") (pin "A2") (pinfunction "A_A2") (pintype "passive"))
      (node (ref "R14") (pin "1") (pinfunction "A_1") (pintype "passive"))
    )
    (net (code "70") (name "Net-(U1-VCONT)") (class "Default")
      (node (ref "C10") (pin "1") (pinfunction "1_1") (pintype "passive"))
      (node (ref "C6") (pin "1") (pinfunction "1_1") (pintype "passive"))
      (node (ref "U1") (pin "3") (pinfunction "VCONT_3") (pintype "passive"))
    )
    (net (code "71") (name "Net-(U2-VCONT)") (class "Default")
      (node (ref "C11") (pin "1") (pinfunction "1_1") (pintype "passive"))
      (node (ref "C7") (pin "1") (pinfunction "1_1") (pintype "passive"))
      (node (ref "U2") (pin "3") (pinfunction "VCONT_3") (pintype "passive"))
    )
    (net (code "72") (name "Net-(U3-VCONT)") (class "Default")
      (node (ref "C12") (pin "1") (pinfunction "1_1") (pintype "passive"))
      (node (ref "C8") (pin "1") (pinfunction "1_1") (pintype "passive"))
      (node (ref "U3") (pin "3") (pinfunction "VCONT_3") (pintype "passive"))
    )
    (net (code "73") (name "Net-(U7-~{PD2})") (class "Default")
      (node (ref "R4") (pin "2") (pinfunction "2_2") (pintype "passive"))
      (node (ref "U7") (pin "4") (pinfunction "~{PD2}_4") (pintype "passive"))
    )
    (net (code "74") (name "Net-(U8-~{PD2})") (class "Default")
      (node (ref "R6") (pin "2") (pinfunction "2_2") (pintype "passive"))
      (node (ref "U8") (pin "4") (pinfunction "~{PD2}_4") (pintype "passive"))
    )
    (net (code "75") (name "Net-(U9-~{PD2})") (class "Default")
      (node (ref "R7") (pin "2") (pinfunction "2_2") (pintype "passive"))
      (node (ref "U9") (pin "4") (pinfunction "~{PD2}_4") (pintype "passive"))
    )
    (net (code "76") (name "Net-(U10-Y)") (class "Default")
      (node (ref "R10") (pin "1") (pinfunction "1_1") (pintype "passive"))
      (node (ref "U10") (pin "4") (pinfunction "Y_4") (pintype "output"))
    )
    (net (code "77") (name "Net-(U11-A)") (class "Default")
      (node (ref "R10") (pin "2") (pinfunction "2_2") (pintype "passive"))
      (node (ref "U11") (pin "2") (pinfunction "A_2") (pintype "bidirectional"))
    )
    (net (code "78") (name "VCC") (class "Default")
      (node (ref "C1") (pin "1") (pinfunction "1_1") (pintype "passive"))
      (node (ref "C14") (pin "1") (pinfunction "1_1") (pintype "passive"))
      (node (ref "C15") (pin "1") (pinfunction "1_1") (pintype "passive"))
      (node (ref "C16") (pin "2") (pinfunction "2_2") (pintype "passive"))
      (node (ref "C17") (pin "1") (pinfunction "1_1") (pintype "passive"))
      (node (ref "C18") (pin "1") (pinfunction "1_1") (pintype "passive"))
      (node (ref "C19") (pin "1") (pinfunction "1_1") (pintype "passive"))
      (node (ref "C2") (pin "1") (pinfunction "1_1") (pintype "passive"))
      (node (ref "C20") (pin "1") (pinfunction "1_1") (pintype "passive"))
      (node (ref "C21") (pin "2") (pinfunction "2_2") (pintype "passive"))
      (node (ref "C22") (pin "1") (pinfunction "1_1") (pintype "passive"))
      (node (ref "C4") (pin "1") (pinfunction "1_1") (pintype "passive"))
      (node (ref "C5") (pin "1") (pinfunction "1_1") (pintype "passive"))
      (node (ref "DIO_HSA") (pin "10") (pinfunction "10_10") (pintype "bidirectional"))
      (node (ref "DIO_HSB") (pin "10") (pinfunction "10_10") (pintype "bidirectional"))
      (node (ref "R13") (pin "2") (pinfunction "W_2") (pintype "passive"))
      (node (ref "R13") (pin "3") (pinfunction "E_3") (pintype "passive"))
      (node (ref "R14") (pin "2") (pinfunction "W_2") (pintype "passive"))
      (node (ref "R14") (pin "3") (pinfunction "E_3") (pintype "passive"))
      (node (ref "R4") (pin "1") (pinfunction "1_1") (pintype "passive"))
      (node (ref "R6") (pin "1") (pinfunction "1_1") (pintype "passive"))
      (node (ref "R7") (pin "1") (pinfunction "1_1") (pintype "passive"))
      (node (ref "TETHER") (pin "12") (pinfunction "12_12") (pintype "bidirectional"))
      (node (ref "TP1") (pin "TP") (pinfunction "TP_TP") (pintype "input"))
      (node (ref "TP10") (pin "1") (pinfunction "1_1") (pintype "passive"))
      (node (ref "TP3") (pin "TP") (pinfunction "TP_TP") (pintype "input"))
      (node (ref "TP9") (pin "1") (pinfunction "1_1") (pintype "passive"))
      (node (ref "U1") (pin "1") (pinfunction "VDD_1") (pintype "power_in"))
      (node (ref "U1") (pin "10") (pinfunction "RES1_10") (pintype "passive"))
      (node (ref "U1") (pin "9") (pinfunction "VDD_9") (pintype "power_in"))
      (node (ref "U10") (pin "5") (pinfunction "VCC_5") (pintype "power_in"))
      (node (ref "U2") (pin "1") (pinfunction "VDD_1") (pintype "power_in"))
      (node (ref "U2") (pin "10") (pinfunction "RES1_10") (pintype "passive"))
      (node (ref "U2") (pin "9") (pinfunction "VDD_9") (pintype "power_in"))
      (node (ref "U3") (pin "1") (pinfunction "VDD_1") (pintype "power_in"))
      (node (ref "U3") (pin "10") (pinfunction "RES1_10") (pintype "passive"))
      (node (ref "U3") (pin "9") (pinfunction "VDD_9") (pintype "power_in"))
      (node (ref "U4") (pin "VS1") (pinfunction "VS1_VS1") (pintype "bidirectional"))
      (node (ref "U4") (pin "VS2") (pinfunction "VS2_VS2") (pintype "bidirectional"))
      (node (ref "U5") (pin "VCC") (pinfunction "VCC_VCC") (pintype "power_in"))
      (node (ref "U6") (pin "VCC") (pinfunction "VCC_VCC") (pintype "power_in"))
      (node (ref "U7") (pin "5") (pinfunction "~{PD1}_5") (pintype "passive"))
      (node (ref "U7") (pin "8") (pinfunction "VCC_8") (pintype "power_in"))
      (node (ref "U8") (pin "5") (pinfunction "~{PD1}_5") (pintype "passive"))
      (node (ref "U8") (pin "8") (pinfunction "VCC_8") (pintype "power_in"))
      (node (ref "U9") (pin "5") (pinfunction "~{PD1}_5") (pintype "passive"))
      (node (ref "U9") (pin "8") (pinfunction "VCC_8") (pintype "power_in"))
    )
    (net (code "79") (name "unconnected-(MECH_E0B-Pad1)") (class "Default")
      (node (ref "MECH_E0B") (pin "1") (pinfunction "1_1") (pintype "bidirectional"))
    )
    (net (code "80") (name "unconnected-(MECH_E0B-Pad2)") (class "Default")
      (node (ref "MECH_E0B") (pin "2") (pinfunction "2_2") (pintype "bidirectional"))
    )
    (net (code "81") (name "unconnected-(MECH_E0B-Pad3)") (class "Default")
      (node (ref "MECH_E0B") (pin "3") (pinfunction "3_3") (pintype "bidirectional"))
    )
    (net (code "82") (name "unconnected-(MECH_E0B-Pad4)") (class "Default")
      (node (ref "MECH_E0B") (pin "4") (pinfunction "4_4") (pintype "bidirectional"))
    )
    (net (code "83") (name "unconnected-(MECH_E0B-Pad5)") (class "Default")
      (node (ref "MECH_E0B") (pin "5") (pinfunction "5_5") (pintype "bidirectional"))
    )
    (net (code "84") (name "unconnected-(MECH_E0B-Pad6)") (class "Default")
      (node (ref "MECH_E0B") (pin "6") (pinfunction "6_6") (pintype "bidirectional"))
    )
    (net (code "85") (name "unconnected-(MECH_E0B-Pad7)") (class "Default")
      (node (ref "MECH_E0B") (pin "7") (pinfunction "7_7") (pintype "bidirectional"))
    )
    (net (code "86") (name "unconnected-(MECH_E0B-Pad8)") (class "Default")
      (node (ref "MECH_E0B") (pin "8") (pinfunction "8_8") (pintype "bidirectional"))
    )
    (net (code "87") (name "unconnected-(MECH_E0B-Pad9)") (class "Default")
      (node (ref "MECH_E0B") (pin "9") (pinfunction "9_9") (pintype "bidirectional"))
    )
    (net (code "88") (name "unconnected-(MECH_E0B-Pad10)") (class "Default")
      (node (ref "MECH_E0B") (pin "10") (pinfunction "10_10") (pintype "bidirectional"))
    )
    (net (code "89") (name "unconnected-(MECH_E0B-Pad11)") (class "Default")
      (node (ref "MECH_E0B") (pin "11") (pinfunction "11_11") (pintype "bidirectional"))
    )
    (net (code "90") (name "unconnected-(MECH_E0B-Pad12)") (class "Default")
      (node (ref "MECH_E0B") (pin "12") (pinfunction "12_12") (pintype "bidirectional"))
    )
    (net (code "91") (name "unconnected-(MECH_E0B-Pad13)") (class "Default")
      (node (ref "MECH_E0B") (pin "13") (pinfunction "13_13") (pintype "bidirectional"))
    )
    (net (code "92") (name "unconnected-(MECH_E0B-Pad14)") (class "Default")
      (node (ref "MECH_E0B") (pin "14") (pinfunction "14_14") (pintype "bidirectional"))
    )
    (net (code "93") (name "unconnected-(MECH_E0B-Pad15)") (class "Default")
      (node (ref "MECH_E0B") (pin "15") (pinfunction "15_15") (pintype "bidirectional"))
    )
    (net (code "94") (name "unconnected-(MECH_E0B-Pad16)") (class "Default")
      (node (ref "MECH_E0B") (pin "16") (pinfunction "16_16") (pintype "bidirectional"))
    )
    (net (code "95") (name "unconnected-(MECH_E0B-Pad17)") (class "Default")
      (node (ref "MECH_E0B") (pin "17") (pinfunction "17_17") (pintype "bidirectional"))
    )
    (net (code "96") (name "unconnected-(MECH_E0B-Pad18)") (class "Default")
      (node (ref "MECH_E0B") (pin "18") (pinfunction "18_18") (pintype "bidirectional"))
    )
    (net (code "97") (name "unconnected-(MECH_E0B-Pad19)") (class "Default")
      (node (ref "MECH_E0B") (pin "19") (pinfunction "19_19") (pintype "bidirectional"))
    )
    (net (code "98") (name "unconnected-(MECH_E0B-Pad20)") (class "Default")
      (node (ref "MECH_E0B") (pin "20") (pinfunction "20_20") (pintype "bidirectional"))
    )
    (net (code "99") (name "unconnected-(MECH_E0B-Pad21)") (class "Default")
      (node (ref "MECH_E0B") (pin "21") (pinfunction "21_21") (pintype "bidirectional"))
    )
    (net (code "100") (name "unconnected-(MECH_E0B-Pad22)") (class "Default")
      (node (ref "MECH_E0B") (pin "22") (pinfunction "22_22") (pintype "bidirectional"))
    )
    (net (code "101") (name "unconnected-(MECH_E0B-Pad23)") (class "Default")
      (node (ref "MECH_E0B") (pin "23") (pinfunction "23_23") (pintype "bidirectional"))
    )
    (net (code "102") (name "unconnected-(MECH_E0B-Pad24)") (class "Default")
      (node (ref "MECH_E0B") (pin "24") (pinfunction "24_24") (pintype "bidirectional"))
    )
    (net (code "103") (name "unconnected-(MECH_E0B-Pad25)") (class "Default")
      (node (ref "MECH_E0B") (pin "25") (pinfunction "25_25") (pintype "bidirectional"))
    )
    (net (code "104") (name "unconnected-(MECH_E0B-Pad26)") (class "Default")
      (node (ref "MECH_E0B") (pin "26") (pinfunction "26_26") (pintype "bidirectional"))
    )
    (net (code "105") (name "unconnected-(MECH_E0B-Pad27)") (class "Default")
      (node (ref "MECH_E0B") (pin "27") (pinfunction "27_27") (pintype "bidirectional"))
    )
    (net (code "106") (name "unconnected-(MECH_E0B-Pad28)") (class "Default")
      (node (ref "MECH_E0B") (pin "28") (pinfunction "28_28") (pintype "bidirectional"))
    )
    (net (code "107") (name "unconnected-(MECH_E0B-Pad29)") (class "Default")
      (node (ref "MECH_E0B") (pin "29") (pinfunction "29_29") (pintype "bidirectional"))
    )
    (net (code "108") (name "unconnected-(MECH_E0B-Pad30)") (class "Default")
      (node (ref "MECH_E0B") (pin "30") (pinfunction "30_30") (pintype "bidirectional"))
    )
    (net (code "109") (name "unconnected-(MECH_E0B-Pad31)") (class "Default")
      (node (ref "MECH_E0B") (pin "31") (pinfunction "31_31") (pintype "bidirectional"))
    )
    (net (code "110") (name "unconnected-(MECH_E0B-Pad32)") (class "Default")
      (node (ref "MECH_E0B") (pin "32") (pinfunction "32_32") (pintype "bidirectional"))
    )
    (net (code "111") (name "unconnected-(MECH_E0B-Pad33)") (class "Default")
      (node (ref "MECH_E0B") (pin "33") (pinfunction "33_33") (pintype "bidirectional"))
    )
    (net (code "112") (name "unconnected-(MECH_E0B-Pad34)") (class "Default")
      (node (ref "MECH_E0B") (pin "34") (pinfunction "34_34") (pintype "bidirectional"))
    )
    (net (code "113") (name "unconnected-(MECH_E0B-Pad35)") (class "Default")
      (node (ref "MECH_E0B") (pin "35") (pinfunction "35_35") (pintype "bidirectional"))
    )
    (net (code "114") (name "unconnected-(MECH_E0B-Pad36)") (class "Default")
      (node (ref "MECH_E0B") (pin "36") (pinfunction "36_36") (pintype "bidirectional"))
    )
    (net (code "115") (name "unconnected-(MECH_E0B-Pad37)") (class "Default")
      (node (ref "MECH_E0B") (pin "37") (pinfunction "37_37") (pintype "bidirectional"))
    )
    (net (code "116") (name "unconnected-(MECH_E0B-Pad38)") (class "Default")
      (node (ref "MECH_E0B") (pin "38") (pinfunction "38_38") (pintype "bidirectional"))
    )
    (net (code "117") (name "unconnected-(MECH_E0B-Pad39)") (class "Default")
      (node (ref "MECH_E0B") (pin "39") (pinfunction "39_39") (pintype "bidirectional"))
    )
    (net (code "118") (name "unconnected-(MECH_E0B-Pad40)") (class "Default")
      (node (ref "MECH_E0B") (pin "40") (pinfunction "40_40") (pintype "bidirectional"))
    )
    (net (code "119") (name "unconnected-(MECH_E0B-Pad41)") (class "Default")
      (node (ref "MECH_E0B") (pin "41") (pinfunction "41_41") (pintype "bidirectional"))
    )
    (net (code "120") (name "unconnected-(MECH_E0B-Pad42)") (class "Default")
      (node (ref "MECH_E0B") (pin "42") (pinfunction "42_42") (pintype "bidirectional"))
    )
    (net (code "121") (name "unconnected-(MECH_E0B-Pad43)") (class "Default")
      (node (ref "MECH_E0B") (pin "43") (pinfunction "43_43") (pintype "bidirectional"))
    )
    (net (code "122") (name "unconnected-(MECH_E0B-Pad44)") (class "Default")
      (node (ref "MECH_E0B") (pin "44") (pinfunction "44_44") (pintype "bidirectional"))
    )
    (net (code "123") (name "unconnected-(MECH_E0B-Pad45)") (class "Default")
      (node (ref "MECH_E0B") (pin "45") (pinfunction "45_45") (pintype "bidirectional"))
    )
    (net (code "124") (name "unconnected-(MECH_E0B-Pad46)") (class "Default")
      (node (ref "MECH_E0B") (pin "46") (pinfunction "46_46") (pintype "bidirectional"))
    )
    (net (code "125") (name "unconnected-(MECH_E0B-Pad47)") (class "Default")
      (node (ref "MECH_E0B") (pin "47") (pinfunction "47_47") (pintype "bidirectional"))
    )
    (net (code "126") (name "unconnected-(MECH_E0B-Pad48)") (class "Default")
      (node (ref "MECH_E0B") (pin "48") (pinfunction "48_48") (pintype "bidirectional"))
    )
    (net (code "127") (name "unconnected-(MECH_E0B-Pad49)") (class "Default")
      (node (ref "MECH_E0B") (pin "49") (pinfunction "49_49") (pintype "bidirectional"))
    )
    (net (code "128") (name "unconnected-(MECH_E0B-Pad50)") (class "Default")
      (node (ref "MECH_E0B") (pin "50") (pinfunction "50_50") (pintype "bidirectional"))
    )
    (net (code "129") (name "unconnected-(MECH_E0B-Pad51)") (class "Default")
      (node (ref "MECH_E0B") (pin "51") (pinfunction "51_51") (pintype "bidirectional"))
    )
    (net (code "130") (name "unconnected-(MECH_E0B-Pad52)") (class "Default")
      (node (ref "MECH_E0B") (pin "52") (pinfunction "52_52") (pintype "bidirectional"))
    )
    (net (code "131") (name "unconnected-(MECH_E0B-Pad53)") (class "Default")
      (node (ref "MECH_E0B") (pin "53") (pinfunction "53_53") (pintype "bidirectional"))
    )
    (net (code "132") (name "unconnected-(MECH_E0B-Pad54)") (class "Default")
      (node (ref "MECH_E0B") (pin "54") (pinfunction "54_54") (pintype "bidirectional"))
    )
    (net (code "133") (name "unconnected-(MECH_E0B-Pad55)") (class "Default")
      (node (ref "MECH_E0B") (pin "55") (pinfunction "55_55") (pintype "bidirectional"))
    )
    (net (code "134") (name "unconnected-(MECH_E0B-Pad56)") (class "Default")
      (node (ref "MECH_E0B") (pin "56") (pinfunction "56_56") (pintype "bidirectional"))
    )
    (net (code "135") (name "unconnected-(MECH_E0B-Pad57)") (class "Default")
      (node (ref "MECH_E0B") (pin "57") (pinfunction "57_57") (pintype "bidirectional"))
    )
    (net (code "136") (name "unconnected-(MECH_E0B-Pad58)") (class "Default")
      (node (ref "MECH_E0B") (pin "58") (pinfunction "58_58") (pintype "bidirectional"))
    )
    (net (code "137") (name "unconnected-(MECH_E0B-Pad59)") (class "Default")
      (node (ref "MECH_E0B") (pin "59") (pinfunction "59_59") (pintype "bidirectional"))
    )
    (net (code "138") (name "unconnected-(MECH_E0B-Pad60)") (class "Default")
      (node (ref "MECH_E0B") (pin "60") (pinfunction "60_60") (pintype "bidirectional"))
    )
    (net (code "139") (name "unconnected-(MECH_E0B-Pad61)") (class "Default")
      (node (ref "MECH_E0B") (pin "61") (pinfunction "61_61") (pintype "bidirectional"))
    )
    (net (code "140") (name "unconnected-(MECH_E0B-Pad62)") (class "Default")
      (node (ref "MECH_E0B") (pin "62") (pinfunction "62_62") (pintype "bidirectional"))
    )
    (net (code "141") (name "unconnected-(MECH_E0B-Pad63)") (class "Default")
      (node (ref "MECH_E0B") (pin "63") (pinfunction "63_63") (pintype "bidirectional"))
    )
    (net (code "142") (name "unconnected-(MECH_E0B-Pad64)") (class "Default")
      (node (ref "MECH_E0B") (pin "64") (pinfunction "64_64") (pintype "bidirectional"))
    )
    (net (code "143") (name "unconnected-(MECH_E0B-Pad65)") (class "Default")
      (node (ref "MECH_E0B") (pin "65") (pinfunction "65_65") (pintype "bidirectional"))
    )
    (net (code "144") (name "unconnected-(MECH_E0B-Pad66)") (class "Default")
      (node (ref "MECH_E0B") (pin "66") (pinfunction "66_66") (pintype "bidirectional"))
    )
    (net (code "145") (name "unconnected-(MECH_E0B-Pad67)") (class "Default")
      (node (ref "MECH_E0B") (pin "67") (pinfunction "67_67") (pintype "bidirectional"))
    )
    (net (code "146") (name "unconnected-(MECH_E0B-Pad68)") (class "Default")
      (node (ref "MECH_E0B") (pin "68") (pinfunction "68_68") (pintype "bidirectional"))
    )
    (net (code "147") (name "unconnected-(MECH_E0B-Pad69)") (class "Default")
      (node (ref "MECH_E0B") (pin "69") (pinfunction "69_69") (pintype "bidirectional"))
    )
    (net (code "148") (name "unconnected-(MECH_E0B-Pad70)") (class "Default")
      (node (ref "MECH_E0B") (pin "70") (pinfunction "70_70") (pintype "bidirectional"))
    )
    (net (code "149") (name "unconnected-(MECH_W0B-Pad1)") (class "Default")
      (node (ref "MECH_W0B") (pin "1") (pinfunction "1_1") (pintype "bidirectional"))
    )
    (net (code "150") (name "unconnected-(MECH_W0B-Pad2)") (class "Default")
      (node (ref "MECH_W0B") (pin "2") (pinfunction "2_2") (pintype "bidirectional"))
    )
    (net (code "151") (name "unconnected-(MECH_W0B-Pad3)") (class "Default")
      (node (ref "MECH_W0B") (pin "3") (pinfunction "3_3") (pintype "bidirectional"))
    )
    (net (code "152") (name "unconnected-(MECH_W0B-Pad4)") (class "Default")
      (node (ref "MECH_W0B") (pin "4") (pinfunction "4_4") (pintype "bidirectional"))
    )
    (net (code "153") (name "unconnected-(MECH_W0B-Pad5)") (class "Default")
      (node (ref "MECH_W0B") (pin "5") (pinfunction "5_5") (pintype "bidirectional"))
    )
    (net (code "154") (name "unconnected-(MECH_W0B-Pad6)") (class "Default")
      (node (ref "MECH_W0B") (pin "6") (pinfunction "6_6") (pintype "bidirectional"))
    )
    (net (code "155") (name "unconnected-(MECH_W0B-Pad7)") (class "Default")
      (node (ref "MECH_W0B") (pin "7") (pinfunction "7_7") (pintype "bidirectional"))
    )
    (net (code "156") (name "unconnected-(MECH_W0B-Pad8)") (class "Default")
      (node (ref "MECH_W0B") (pin "8") (pinfunction "8_8") (pintype "bidirectional"))
    )
    (net (code "157") (name "unconnected-(MECH_W0B-Pad9)") (class "Default")
      (node (ref "MECH_W0B") (pin "9") (pinfunction "9_9") (pintype "bidirectional"))
    )
    (net (code "158") (name "unconnected-(MECH_W0B-Pad10)") (class "Default")
      (node (ref "MECH_W0B") (pin "10") (pinfunction "10_10") (pintype "bidirectional"))
    )
    (net (code "159") (name "unconnected-(MECH_W0B-Pad11)") (class "Default")
      (node (ref "MECH_W0B") (pin "11") (pinfunction "11_11") (pintype "bidirectional"))
    )
    (net (code "160") (name "unconnected-(MECH_W0B-Pad12)") (class "Default")
      (node (ref "MECH_W0B") (pin "12") (pinfunction "12_12") (pintype "bidirectional"))
    )
    (net (code "161") (name "unconnected-(MECH_W0B-Pad13)") (class "Default")
      (node (ref "MECH_W0B") (pin "13") (pinfunction "13_13") (pintype "bidirectional"))
    )
    (net (code "162") (name "unconnected-(MECH_W0B-Pad14)") (class "Default")
      (node (ref "MECH_W0B") (pin "14") (pinfunction "14_14") (pintype "bidirectional"))
    )
    (net (code "163") (name "unconnected-(MECH_W0B-Pad15)") (class "Default")
      (node (ref "MECH_W0B") (pin "15") (pinfunction "15_15") (pintype "bidirectional"))
    )
    (net (code "164") (name "unconnected-(MECH_W0B-Pad16)") (class "Default")
      (node (ref "MECH_W0B") (pin "16") (pinfunction "16_16") (pintype "bidirectional"))
    )
    (net (code "165") (name "unconnected-(MECH_W0B-Pad17)") (class "Default")
      (node (ref "MECH_W0B") (pin "17") (pinfunction "17_17") (pintype "bidirectional"))
    )
    (net (code "166") (name "unconnected-(MECH_W0B-Pad18)") (class "Default")
      (node (ref "MECH_W0B") (pin "18") (pinfunction "18_18") (pintype "bidirectional"))
    )
    (net (code "167") (name "unconnected-(MECH_W0B-Pad19)") (class "Default")
      (node (ref "MECH_W0B") (pin "19") (pinfunction "19_19") (pintype "bidirectional"))
    )
    (net (code "168") (name "unconnected-(MECH_W0B-Pad20)") (class "Default")
      (node (ref "MECH_W0B") (pin "20") (pinfunction "20_20") (pintype "bidirectional"))
    )
    (net (code "169") (name "unconnected-(MECH_W0B-Pad21)") (class "Default")
      (node (ref "MECH_W0B") (pin "21") (pinfunction "21_21") (pintype "bidirectional"))
    )
    (net (code "170") (name "unconnected-(MECH_W0B-Pad22)") (class "Default")
      (node (ref "MECH_W0B") (pin "22") (pinfunction "22_22") (pintype "bidirectional"))
    )
    (net (code "171") (name "unconnected-(MECH_W0B-Pad23)") (class "Default")
      (node (ref "MECH_W0B") (pin "23") (pinfunction "23_23") (pintype "bidirectional"))
    )
    (net (code "172") (name "unconnected-(MECH_W0B-Pad24)") (class "Default")
      (node (ref "MECH_W0B") (pin "24") (pinfunction "24_24") (pintype "bidirectional"))
    )
    (net (code "173") (name "unconnected-(MECH_W0B-Pad25)") (class "Default")
      (node (ref "MECH_W0B") (pin "25") (pinfunction "25_25") (pintype "bidirectional"))
    )
    (net (code "174") (name "unconnected-(MECH_W0B-Pad26)") (class "Default")
      (node (ref "MECH_W0B") (pin "26") (pinfunction "26_26") (pintype "bidirectional"))
    )
    (net (code "175") (name "unconnected-(MECH_W0B-Pad27)") (class "Default")
      (node (ref "MECH_W0B") (pin "27") (pinfunction "27_27") (pintype "bidirectional"))
    )
    (net (code "176") (name "unconnected-(MECH_W0B-Pad28)") (class "Default")
      (node (ref "MECH_W0B") (pin "28") (pinfunction "28_28") (pintype "bidirectional"))
    )
    (net (code "177") (name "unconnected-(MECH_W0B-Pad29)") (class "Default")
      (node (ref "MECH_W0B") (pin "29") (pinfunction "29_29") (pintype "bidirectional"))
    )
    (net (code "178") (name "unconnected-(MECH_W0B-Pad30)") (class "Default")
      (node (ref "MECH_W0B") (pin "30") (pinfunction "30_30") (pintype "bidirectional"))
    )
    (net (code "179") (name "unconnected-(MECH_W0B-Pad31)") (class "Default")
      (node (ref "MECH_W0B") (pin "31") (pinfunction "31_31") (pintype "bidirectional"))
    )
    (net (code "180") (name "unconnected-(MECH_W0B-Pad32)") (class "Default")
      (node (ref "MECH_W0B") (pin "32") (pinfunction "32_32") (pintype "bidirectional"))
    )
    (net (code "181") (name "unconnected-(MECH_W0B-Pad33)") (class "Default")
      (node (ref "MECH_W0B") (pin "33") (pinfunction "33_33") (pintype "bidirectional"))
    )
    (net (code "182") (name "unconnected-(MECH_W0B-Pad34)") (class "Default")
      (node (ref "MECH_W0B") (pin "34") (pinfunction "34_34") (pintype "bidirectional"))
    )
    (net (code "183") (name "unconnected-(MECH_W0B-Pad35)") (class "Default")
      (node (ref "MECH_W0B") (pin "35") (pinfunction "35_35") (pintype "bidirectional"))
    )
    (net (code "184") (name "unconnected-(MECH_W0B-Pad36)") (class "Default")
      (node (ref "MECH_W0B") (pin "36") (pinfunction "36_36") (pintype "bidirectional"))
    )
    (net (code "185") (name "unconnected-(MECH_W0B-Pad37)") (class "Default")
      (node (ref "MECH_W0B") (pin "37") (pinfunction "37_37") (pintype "bidirectional"))
    )
    (net (code "186") (name "unconnected-(MECH_W0B-Pad38)") (class "Default")
      (node (ref "MECH_W0B") (pin "38") (pinfunction "38_38") (pintype "bidirectional"))
    )
    (net (code "187") (name "unconnected-(MECH_W0B-Pad39)") (class "Default")
      (node (ref "MECH_W0B") (pin "39") (pinfunction "39_39") (pintype "bidirectional"))
    )
    (net (code "188") (name "unconnected-(MECH_W0B-Pad40)") (class "Default")
      (node (ref "MECH_W0B") (pin "40") (pinfunction "40_40") (pintype "bidirectional"))
    )
    (net (code "189") (name "unconnected-(MECH_W0B-Pad41)") (class "Default")
      (node (ref "MECH_W0B") (pin "41") (pinfunction "41_41") (pintype "bidirectional"))
    )
    (net (code "190") (name "unconnected-(MECH_W0B-Pad42)") (class "Default")
      (node (ref "MECH_W0B") (pin "42") (pinfunction "42_42") (pintype "bidirectional"))
    )
    (net (code "191") (name "unconnected-(MECH_W0B-Pad43)") (class "Default")
      (node (ref "MECH_W0B") (pin "43") (pinfunction "43_43") (pintype "bidirectional"))
    )
    (net (code "192") (name "unconnected-(MECH_W0B-Pad44)") (class "Default")
      (node (ref "MECH_W0B") (pin "44") (pinfunction "44_44") (pintype "bidirectional"))
    )
    (net (code "193") (name "unconnected-(MECH_W0B-Pad45)") (class "Default")
      (node (ref "MECH_W0B") (pin "45") (pinfunction "45_45") (pintype "bidirectional"))
    )
    (net (code "194") (name "unconnected-(MECH_W0B-Pad46)") (class "Default")
      (node (ref "MECH_W0B") (pin "46") (pinfunction "46_46") (pintype "bidirectional"))
    )
    (net (code "195") (name "unconnected-(MECH_W0B-Pad47)") (class "Default")
      (node (ref "MECH_W0B") (pin "47") (pinfunction "47_47") (pintype "bidirectional"))
    )
    (net (code "196") (name "unconnected-(MECH_W0B-Pad48)") (class "Default")
      (node (ref "MECH_W0B") (pin "48") (pinfunction "48_48") (pintype "bidirectional"))
    )
    (net (code "197") (name "unconnected-(MECH_W0B-Pad49)") (class "Default")
      (node (ref "MECH_W0B") (pin "49") (pinfunction "49_49") (pintype "bidirectional"))
    )
    (net (code "198") (name "unconnected-(MECH_W0B-Pad50)") (class "Default")
      (node (ref "MECH_W0B") (pin "50") (pinfunction "50_50") (pintype "bidirectional"))
    )
    (net (code "199") (name "unconnected-(MECH_W0B-Pad51)") (class "Default")
      (node (ref "MECH_W0B") (pin "51") (pinfunction "51_51") (pintype "bidirectional"))
    )
    (net (code "200") (name "unconnected-(MECH_W0B-Pad52)") (class "Default")
      (node (ref "MECH_W0B") (pin "52") (pinfunction "52_52") (pintype "bidirectional"))
    )
    (net (code "201") (name "unconnected-(MECH_W0B-Pad53)") (class "Default")
      (node (ref "MECH_W0B") (pin "53") (pinfunction "53_53") (pintype "bidirectional"))
    )
    (net (code "202") (name "unconnected-(MECH_W0B-Pad54)") (class "Default")
      (node (ref "MECH_W0B") (pin "54") (pinfunction "54_54") (pintype "bidirectional"))
    )
    (net (code "203") (name "unconnected-(MECH_W0B-Pad55)") (class "Default")
      (node (ref "MECH_W0B") (pin "55") (pinfunction "55_55") (pintype "bidirectional"))
    )
    (net (code "204") (name "unconnected-(MECH_W0B-Pad56)") (class "Default")
      (node (ref "MECH_W0B") (pin "56") (pinfunction "56_56") (pintype "bidirectional"))
    )
    (net (code "205") (name "unconnected-(MECH_W0B-Pad57)") (class "Default")
      (node (ref "MECH_W0B") (pin "57") (pinfunction "57_57") (pintype "bidirectional"))
    )
    (net (code "206") (name "unconnected-(MECH_W0B-Pad58)") (class "Default")
      (node (ref "MECH_W0B") (pin "58") (pinfunction "58_58") (pintype "bidirectional"))
    )
    (net (code "207") (name "unconnected-(MECH_W0B-Pad59)") (class "Default")
      (node (ref "MECH_W0B") (pin "59") (pinfunction "59_59") (pintype "bidirectional"))
    )
    (net (code "208") (name "unconnected-(MECH_W0B-Pad60)") (class "Default")
      (node (ref "MECH_W0B") (pin "60") (pinfunction "60_60") (pintype "bidirectional"))
    )
    (net (code "209") (name "unconnected-(MECH_W0B-Pad61)") (class "Default")
      (node (ref "MECH_W0B") (pin "61") (pinfunction "61_61") (pintype "bidirectional"))
    )
    (net (code "210") (name "unconnected-(MECH_W0B-Pad62)") (class "Default")
      (node (ref "MECH_W0B") (pin "62") (pinfunction "62_62") (pintype "bidirectional"))
    )
    (net (code "211") (name "unconnected-(MECH_W0B-Pad63)") (class "Default")
      (node (ref "MECH_W0B") (pin "63") (pinfunction "63_63") (pintype "bidirectional"))
    )
    (net (code "212") (name "unconnected-(MECH_W0B-Pad64)") (class "Default")
      (node (ref "MECH_W0B") (pin "64") (pinfunction "64_64") (pintype "bidirectional"))
    )
    (net (code "213") (name "unconnected-(MECH_W0B-Pad65)") (class "Default")
      (node (ref "MECH_W0B") (pin "65") (pinfunction "65_65") (pintype "bidirectional"))
    )
    (net (code "214") (name "unconnected-(MECH_W0B-Pad66)") (class "Default")
      (node (ref "MECH_W0B") (pin "66") (pinfunction "66_66") (pintype "bidirectional"))
    )
    (net (code "215") (name "unconnected-(MECH_W0B-Pad67)") (class "Default")
      (node (ref "MECH_W0B") (pin "67") (pinfunction "67_67") (pintype "bidirectional"))
    )
    (net (code "216") (name "unconnected-(MECH_W0B-Pad68)") (class "Default")
      (node (ref "MECH_W0B") (pin "68") (pinfunction "68_68") (pintype "bidirectional"))
    )
    (net (code "217") (name "unconnected-(MECH_W0B-Pad69)") (class "Default")
      (node (ref "MECH_W0B") (pin "69") (pinfunction "69_69") (pintype "bidirectional"))
    )
    (net (code "218") (name "unconnected-(MECH_W0B-Pad70)") (class "Default")
      (node (ref "MECH_W0B") (pin "70") (pinfunction "70_70") (pintype "bidirectional"))
    )
    (net (code "219") (name "unconnected-(U1-RES-Pad5)") (class "Default")
      (node (ref "U1") (pin "5") (pinfunction "RES_5") (pintype "passive"))
    )
    (net (code "220") (name "unconnected-(U2-RES-Pad5)") (class "Default")
      (node (ref "U2") (pin "5") (pinfunction "RES_5") (pintype "passive"))
    )
    (net (code "221") (name "unconnected-(U3-RES-Pad5)") (class "Default")
      (node (ref "U3") (pin "5") (pinfunction "RES_5") (pintype "passive"))
    )
    (net (code "222") (name "unconnected-(U4-PadNC1)") (class "Default")
      (node (ref "U4") (pin "NC1") (pinfunction "NC1_NC1") (pintype "bidirectional"))
    )
    (net (code "223") (name "unconnected-(U4-PadNC2)") (class "Default")
      (node (ref "U4") (pin "NC2") (pinfunction "NC2_NC2") (pintype "bidirectional"))
    )
    (net (code "224") (name "unconnected-(U4-PadNC3)") (class "Default")
      (node (ref "U4") (pin "NC3") (pinfunction "NC3_NC3") (pintype "bidirectional"))
    )
    (net (code "225") (name "unconnected-(U4-PadNC4)") (class "Default")
      (node (ref "U4") (pin "NC4") (pinfunction "NC4_NC4") (pintype "bidirectional"))
    )
    (net (code "226") (name "unconnected-(U4-PadNC5)") (class "Default")
      (node (ref "U4") (pin "NC5") (pinfunction "NC5_NC5") (pintype "bidirectional"))
    )
    (net (code "227") (name "unconnected-(U4-PadNC6)") (class "Default")
      (node (ref "U4") (pin "NC6") (pinfunction "NC6_NC6") (pintype "bidirectional"))
    )
  )
)
